# pnode.net
KiCad netlist of a schematic drawn in EAGLE
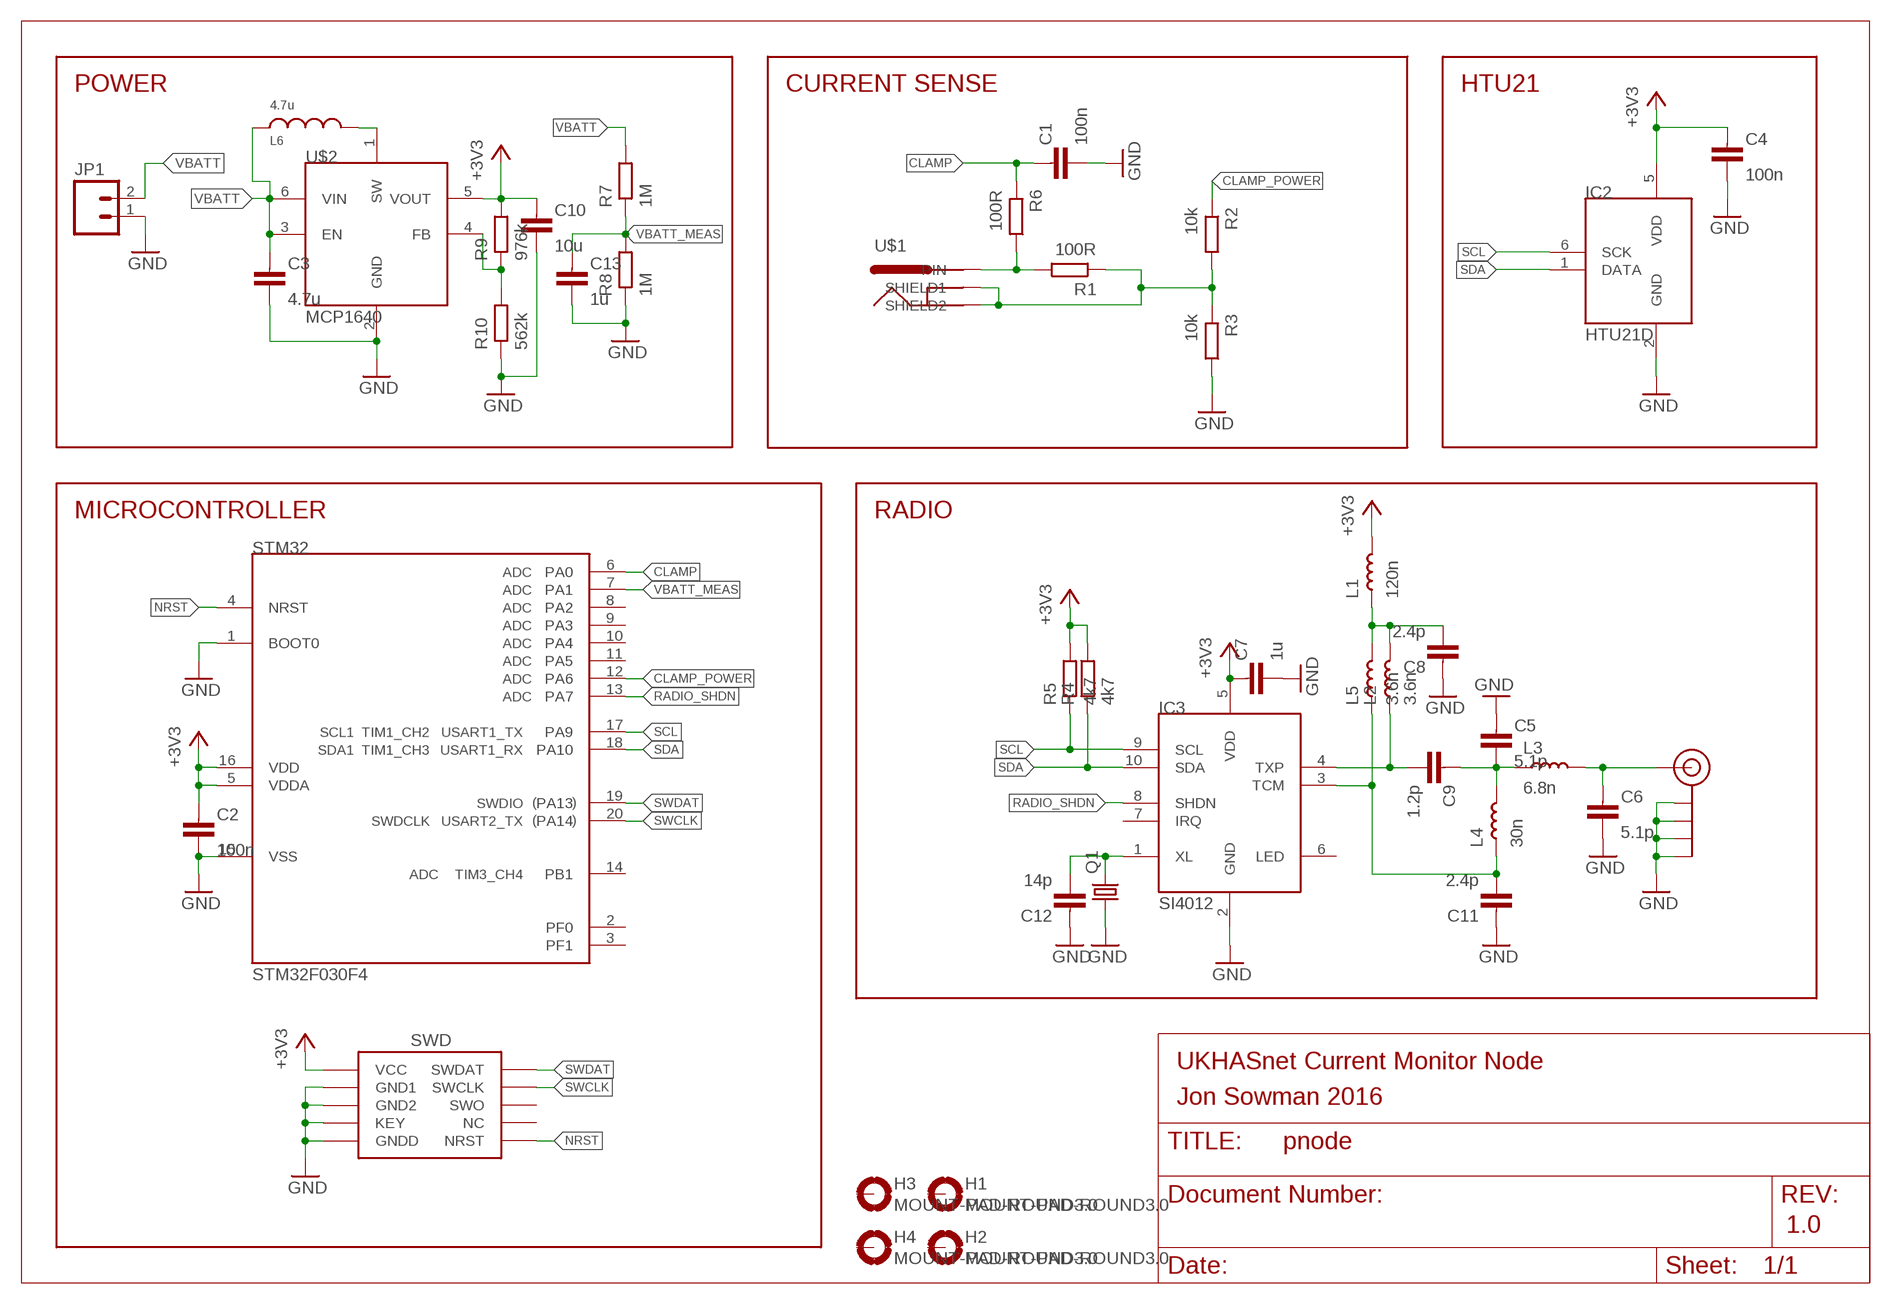
[diagram p0: schematic, sheet 1]

(export (version "E")
  (design (tool "Eeschema 10.0.6"))
  (components
    (comp (ref "C1")
      (value "100n")
      (footprint "eagle-import:C0603-N")
      (libsource (lib "eagle-import") (part "CAPACITOR0603-N"))
    )
    (comp (ref "C2")
      (value "100n")
      (footprint "eagle-import:C0603-N")
      (libsource (lib "eagle-import") (part "CAPACITOR0603-N"))
    )
    (comp (ref "C3")
      (value "4.7u")
      (footprint "eagle-import:C0603-N")
      (libsource (lib "eagle-import") (part "CAPACITOR0603-N"))
    )
    (comp (ref "C4")
      (value "100n")
      (footprint "eagle-import:C0603-N")
      (libsource (lib "eagle-import") (part "CAPACITOR0603-N"))
    )
    (comp (ref "C5")
      (value "5.1p")
      (footprint "eagle-import:C0603-N")
      (libsource (lib "eagle-import") (part "CAPACITOR0603-N"))
    )
    (comp (ref "C6")
      (value "5.1p")
      (footprint "eagle-import:C0603-N")
      (libsource (lib "eagle-import") (part "CAPACITOR0603-N"))
    )
    (comp (ref "C7")
      (value "1u")
      (footprint "eagle-import:C0603-N")
      (libsource (lib "eagle-import") (part "CAPACITOR0603-N"))
    )
    (comp (ref "C8")
      (value "2.4p")
      (footprint "eagle-import:C0603-N")
      (libsource (lib "eagle-import") (part "CAPACITOR0603-N"))
    )
    (comp (ref "C9")
      (value "1.2p")
      (footprint "eagle-import:C0603-N")
      (libsource (lib "eagle-import") (part "CAPACITOR0603-N"))
    )
    (comp (ref "C10")
      (value "10u")
      (footprint "eagle-import:C0603-N")
      (libsource (lib "eagle-import") (part "CAPACITOR0603-N"))
    )
    (comp (ref "C11")
      (value "2.4p")
      (footprint "eagle-import:C0603-N")
      (libsource (lib "eagle-import") (part "CAPACITOR0603-N"))
    )
    (comp (ref "C12")
      (value "14p")
      (footprint "eagle-import:C0603-N")
      (libsource (lib "eagle-import") (part "CAPACITOR0603-N"))
    )
    (comp (ref "C13")
      (value "1u")
      (footprint "eagle-import:C0603-N")
      (libsource (lib "eagle-import") (part "CAPACITOR0603-N"))
    )
    (comp (ref "H1")
      (value "MOUNT-PAD-ROUND3.0")
      (footprint "eagle-import:3,0-PAD")
      (libsource (lib "eagle-import") (part "MOUNT-PAD-ROUND3.0"))
    )
    (comp (ref "H2")
      (value "MOUNT-PAD-ROUND3.0")
      (footprint "eagle-import:3,0-PAD")
      (libsource (lib "eagle-import") (part "MOUNT-PAD-ROUND3.0"))
    )
    (comp (ref "H3")
      (value "MOUNT-PAD-ROUND3.0")
      (footprint "eagle-import:3,0-PAD")
      (libsource (lib "eagle-import") (part "MOUNT-PAD-ROUND3.0"))
    )
    (comp (ref "H4")
      (value "MOUNT-PAD-ROUND3.0")
      (footprint "eagle-import:3,0-PAD")
      (libsource (lib "eagle-import") (part "MOUNT-PAD-ROUND3.0"))
    )
    (comp (ref "IC2")
      (value "HTU21D")
      (footprint "eagle-import:DFN6-L")
      (libsource (lib "eagle-import") (part "HTU21D"))
    )
    (comp (ref "IC3")
      (value "SI4012")
      (footprint "eagle-import:MSOP10")
      (libsource (lib "eagle-import") (part "SI4012"))
    )
    (comp (ref "J$1")
      (value "SMA_EDGE")
      (footprint "eagle-import:SMA-EDGE")
      (libsource (lib "eagle-import") (part "SMA_EDGE"))
    )
    (comp (ref "JP1")
      (value "M02PTH")
      (footprint "eagle-import:1X02")
      (libsource (lib "eagle-import") (part "M02PTH"))
    )
    (comp (ref "L1")
      (value "120n")
      (footprint "eagle-import:L0603-N")
      (libsource (lib "eagle-import") (part "INDUCTOR0603-N"))
    )
    (comp (ref "L2")
      (value "3.6n")
      (footprint "eagle-import:L0402-N")
      (libsource (lib "eagle-import") (part "INDUCTOR0402-N"))
    )
    (comp (ref "L3")
      (value "6.8n")
      (footprint "eagle-import:L0402-N")
      (libsource (lib "eagle-import") (part "INDUCTOR0402-N"))
    )
    (comp (ref "L4")
      (value "30n")
      (footprint "eagle-import:L0402-N")
      (libsource (lib "eagle-import") (part "INDUCTOR0402-N"))
    )
    (comp (ref "L5")
      (value "3.6n")
      (footprint "eagle-import:L0402-N")
      (libsource (lib "eagle-import") (part "INDUCTOR0402-N"))
    )
    (comp (ref "L6")
      (value "4.7u")
      (footprint "eagle-import:BOURNS_SDE0403A")
      (libsource (lib "eagle-import") (part "BOURNS_SDE0403A"))
    )
    (comp (ref "Q1")
      (value "CRYSTALHC49S")
      (footprint "eagle-import:HC49_S")
      (libsource (lib "eagle-import") (part "CRYSTALHC49S"))
    )
    (comp (ref "R1")
      (value "100R")
      (footprint "eagle-import:R0603-N")
      (libsource (lib "eagle-import") (part "RESISTOR0603-N"))
    )
    (comp (ref "R2")
      (value "10k")
      (footprint "eagle-import:R0603-N")
      (libsource (lib "eagle-import") (part "RESISTOR0603-N"))
    )
    (comp (ref "R3")
      (value "10k")
      (footprint "eagle-import:R0603-N")
      (libsource (lib "eagle-import") (part "RESISTOR0603-N"))
    )
    (comp (ref "R4")
      (value "4k7")
      (footprint "eagle-import:R0603-N")
      (libsource (lib "eagle-import") (part "RESISTOR0603-N"))
    )
    (comp (ref "R5")
      (value "4k7")
      (footprint "eagle-import:R0603-N")
      (libsource (lib "eagle-import") (part "RESISTOR0603-N"))
    )
    (comp (ref "R6")
      (value "100R")
      (footprint "eagle-import:R0603-N")
      (libsource (lib "eagle-import") (part "RESISTOR0603-N"))
    )
    (comp (ref "R7")
      (value "1M")
      (footprint "eagle-import:R0603-N")
      (libsource (lib "eagle-import") (part "RESISTOR0603-N"))
    )
    (comp (ref "R8")
      (value "1M")
      (footprint "eagle-import:R0603-N")
      (libsource (lib "eagle-import") (part "RESISTOR0603-N"))
    )
    (comp (ref "R9")
      (value "976k")
      (footprint "eagle-import:R0603-N")
      (libsource (lib "eagle-import") (part "RESISTOR0603-N"))
    )
    (comp (ref "R10")
      (value "562k")
      (footprint "eagle-import:R0603-N")
      (libsource (lib "eagle-import") (part "RESISTOR0603-N"))
    )
    (comp (ref "STM32")
      (value "STM32F030F4")
      (footprint "eagle-import:TSSOP20")
      (libsource (lib "eagle-import") (part "STM32F030F4"))
    )
    (comp (ref "U$1")
      (value "13MM_DC_JACKPTH")
      (footprint "eagle-import:13MM_DC_JACK")
      (libsource (lib "eagle-import") (part "13MM_DC_JACKPTH"))
    )
    (comp (ref "U$2")
      (value "MCP1640")
      (footprint "eagle-import:SOT23-6")
      (libsource (lib "eagle-import") (part "MCP1640"))
    )
    (comp (ref "U$3")
      (value "SWD_PTH_SHROUD")
      (footprint "eagle-import:SWD_PTH_SHROUD")
      (libsource (lib "eagle-import") (part "SWD_PTH_SHROUD"))
    )
  )
  (nets
    (net (code "1") (name "+3V3") (class "Default")
      (node (ref "C10") (pin "1") (pinfunction "1_1") (pintype "passive"))
      (node (ref "C2") (pin "1") (pinfunction "1_1") (pintype "passive"))
      (node (ref "C4") (pin "1") (pinfunction "1_1") (pintype "passive"))
      (node (ref "C7") (pin "1") (pinfunction "1_1") (pintype "passive"))
      (node (ref "IC2") (pin "5") (pinfunction "VDD_5") (pintype "power_in"))
      (node (ref "IC3") (pin "5") (pinfunction "VDD_5") (pintype "power_in"))
      (node (ref "L1") (pin "2") (pinfunction "P$2_2") (pintype "passive"))
      (node (ref "R4") (pin "2") (pinfunction "P$2_2") (pintype "passive"))
      (node (ref "R5") (pin "2") (pinfunction "P$2_2") (pintype "passive"))
      (node (ref "R9") (pin "2") (pinfunction "P$2_2") (pintype "passive"))
      (node (ref "STM32") (pin "16") (pinfunction "VDD_16") (pintype "power_in"))
      (node (ref "STM32") (pin "5") (pinfunction "VDDA_5") (pintype "power_in"))
      (node (ref "U$2") (pin "5") (pinfunction "VOUT_5") (pintype "output"))
      (node (ref "U$3") (pin "1") (pinfunction "VCC_1") (pintype "power_in"))
    )
    (net (code "2") (name "CLAMP") (class "Default")
      (node (ref "C1") (pin "1") (pinfunction "1_1") (pintype "passive"))
      (node (ref "R6") (pin "1") (pinfunction "P$1_1") (pintype "passive"))
      (node (ref "STM32") (pin "6") (pinfunction "PA0_6") (pintype "bidirectional"))
    )
    (net (code "3") (name "CLAMP_POWER") (class "Default")
      (node (ref "R2") (pin "1") (pinfunction "P$1_1") (pintype "passive"))
      (node (ref "STM32") (pin "12") (pinfunction "PA6_12") (pintype "bidirectional"))
    )
    (net (code "4") (name "GND") (class "Default")
      (node (ref "C1") (pin "2") (pinfunction "2_2") (pintype "passive"))
      (node (ref "C10") (pin "2") (pinfunction "2_2") (pintype "passive"))
      (node (ref "C11") (pin "1") (pinfunction "1_1") (pintype "passive"))
      (node (ref "C12") (pin "1") (pinfunction "1_1") (pintype "passive"))
      (node (ref "C13") (pin "2") (pinfunction "2_2") (pintype "passive"))
      (node (ref "C2") (pin "2") (pinfunction "2_2") (pintype "passive"))
      (node (ref "C3") (pin "2") (pinfunction "2_2") (pintype "passive"))
      (node (ref "C4") (pin "2") (pinfunction "2_2") (pintype "passive"))
      (node (ref "C5") (pin "1") (pinfunction "1_1") (pintype "passive"))
      (node (ref "C6") (pin "2") (pinfunction "2_2") (pintype "passive"))
      (node (ref "C7") (pin "2") (pinfunction "2_2") (pintype "passive"))
      (node (ref "C8") (pin "1") (pinfunction "1_1") (pintype "passive"))
      (node (ref "IC2") (pin "2") (pinfunction "GND_2") (pintype "power_in"))
      (node (ref "IC3") (pin "2") (pinfunction "GND_2") (pintype "power_in"))
      (node (ref "J$1") (pin "GND@0") (pinfunction "GND_GND@0") (pintype "bidirectional"))
      (node (ref "J$1") (pin "GND@1") (pinfunction "GND_GND@1") (pintype "bidirectional"))
      (node (ref "J$1") (pin "GND@2") (pinfunction "GND_GND@2") (pintype "bidirectional"))
      (node (ref "J$1") (pin "GND@3") (pinfunction "GND_GND@3") (pintype "bidirectional"))
      (node (ref "JP1") (pin "1") (pinfunction "1_1") (pintype "passive"))
      (node (ref "Q1") (pin "1") (pinfunction "1_1") (pintype "passive"))
      (node (ref "R10") (pin "1") (pinfunction "P$1_1") (pintype "passive"))
      (node (ref "R3") (pin "2") (pinfunction "P$2_2") (pintype "passive"))
      (node (ref "R8") (pin "1") (pinfunction "P$1_1") (pintype "passive"))
      (node (ref "STM32") (pin "1") (pinfunction "BOOT0_1") (pintype "input"))
      (node (ref "STM32") (pin "15") (pinfunction "VSS_15") (pintype "power_in"))
      (node (ref "U$2") (pin "2") (pinfunction "GND_2") (pintype "power_in"))
      (node (ref "U$3") (pin "3") (pinfunction "GND1_3") (pintype "power_in"))
      (node (ref "U$3") (pin "5") (pinfunction "GND2_5") (pintype "power_in"))
      (node (ref "U$3") (pin "7") (pinfunction "KEY_7") (pintype "bidirectional"))
      (node (ref "U$3") (pin "9") (pinfunction "GNDD_9") (pintype "power_in"))
    )
    (net (code "5") (name "NRST") (class "Default")
      (node (ref "STM32") (pin "4") (pinfunction "NRST_4") (pintype "input"))
      (node (ref "U$3") (pin "10") (pinfunction "NRST_10") (pintype "bidirectional"))
    )
    (net (code "6") (name "Net-(IC3-TCM)") (class "Default")
      (node (ref "C11") (pin "2") (pinfunction "2_2") (pintype "passive"))
      (node (ref "IC3") (pin "3") (pinfunction "TCM_3") (pintype "output"))
      (node (ref "L4") (pin "1") (pinfunction "P$1_1") (pintype "passive"))
      (node (ref "L5") (pin "1") (pinfunction "P$1_1") (pintype "passive"))
    )
    (net (code "7") (name "Net-(IC3-TXP)") (class "Default")
      (node (ref "C9") (pin "2") (pinfunction "2_2") (pintype "passive"))
      (node (ref "IC3") (pin "4") (pinfunction "TXP_4") (pintype "output"))
      (node (ref "L2") (pin "1") (pinfunction "P$1_1") (pintype "passive"))
    )
    (net (code "8") (name "Net-(IC3-XL)") (class "Default")
      (node (ref "C12") (pin "2") (pinfunction "2_2") (pintype "passive"))
      (node (ref "IC3") (pin "1") (pinfunction "XL_1") (pintype "bidirectional"))
      (node (ref "Q1") (pin "2") (pinfunction "2_2") (pintype "passive"))
    )
    (net (code "9") (name "Net-(J$1-SIGNAL)") (class "Default")
      (node (ref "C6") (pin "1") (pinfunction "1_1") (pintype "passive"))
      (node (ref "J$1") (pin "SIG") (pinfunction "SIGNAL_SIG") (pintype "bidirectional"))
      (node (ref "L3") (pin "2") (pinfunction "P$2_2") (pintype "passive"))
    )
    (net (code "10") (name "Net-(L1-P$1)") (class "Default")
      (node (ref "C8") (pin "2") (pinfunction "2_2") (pintype "passive"))
      (node (ref "L1") (pin "1") (pinfunction "P$1_1") (pintype "passive"))
      (node (ref "L2") (pin "2") (pinfunction "P$2_2") (pintype "passive"))
      (node (ref "L5") (pin "2") (pinfunction "P$2_2") (pintype "passive"))
    )
    (net (code "11") (name "Net-(L3-P$1)") (class "Default")
      (node (ref "C5") (pin "2") (pinfunction "2_2") (pintype "passive"))
      (node (ref "C9") (pin "1") (pinfunction "1_1") (pintype "passive"))
      (node (ref "L3") (pin "1") (pinfunction "P$1_1") (pintype "passive"))
      (node (ref "L4") (pin "2") (pinfunction "P$2_2") (pintype "passive"))
    )
    (net (code "12") (name "Net-(R1-P$1)") (class "Default")
      (node (ref "R1") (pin "1") (pinfunction "P$1_1") (pintype "passive"))
      (node (ref "R2") (pin "2") (pinfunction "P$2_2") (pintype "passive"))
      (node (ref "R3") (pin "1") (pinfunction "P$1_1") (pintype "passive"))
      (node (ref "U$1") (pin "2") (pinfunction "SHIELD1_2") (pintype "bidirectional"))
      (node (ref "U$1") (pin "3") (pinfunction "SHIELD2_3") (pintype "bidirectional"))
    )
    (net (code "13") (name "Net-(R1-P$2)") (class "Default")
      (node (ref "R1") (pin "2") (pinfunction "P$2_2") (pintype "passive"))
      (node (ref "R6") (pin "2") (pinfunction "P$2_2") (pintype "passive"))
      (node (ref "U$1") (pin "1") (pinfunction "PIN_1") (pintype "bidirectional"))
    )
    (net (code "14") (name "Net-(R10-P$2)") (class "Default")
      (node (ref "R10") (pin "2") (pinfunction "P$2_2") (pintype "passive"))
      (node (ref "R9") (pin "1") (pinfunction "P$1_1") (pintype "passive"))
      (node (ref "U$2") (pin "4") (pinfunction "FB_4") (pintype "input"))
    )
    (net (code "15") (name "Net-(U$2-SW)") (class "Default")
      (node (ref "L6") (pin "P$2") (pinfunction "P$2_P$2") (pintype "bidirectional"))
      (node (ref "U$2") (pin "1") (pinfunction "SW_1") (pintype "input"))
    )
    (net (code "16") (name "RADIO_SHDN") (class "Default")
      (node (ref "IC3") (pin "8") (pinfunction "SHDN_8") (pintype "input"))
      (node (ref "STM32") (pin "13") (pinfunction "PA7_13") (pintype "bidirectional"))
    )
    (net (code "17") (name "SCL") (class "Default")
      (node (ref "IC2") (pin "6") (pinfunction "SCK_6") (pintype "input"))
      (node (ref "IC3") (pin "9") (pinfunction "SCL_9") (pintype "input"))
      (node (ref "R5") (pin "1") (pinfunction "P$1_1") (pintype "passive"))
      (node (ref "STM32") (pin "17") (pinfunction "PA9_17") (pintype "bidirectional"))
    )
    (net (code "18") (name "SDA") (class "Default")
      (node (ref "IC2") (pin "1") (pinfunction "DATA_1") (pintype "bidirectional"))
      (node (ref "IC3") (pin "10") (pinfunction "SDA_10") (pintype "bidirectional"))
      (node (ref "R4") (pin "1") (pinfunction "P$1_1") (pintype "passive"))
      (node (ref "STM32") (pin "18") (pinfunction "PA10_18") (pintype "bidirectional"))
    )
    (net (code "19") (name "SWCLK") (class "Default")
      (node (ref "STM32") (pin "20") (pinfunction "PA14_20") (pintype "bidirectional"))
      (node (ref "U$3") (pin "4") (pinfunction "SWCLK_4") (pintype "bidirectional"))
    )
    (net (code "20") (name "SWDAT") (class "Default")
      (node (ref "STM32") (pin "19") (pinfunction "PA13_19") (pintype "bidirectional"))
      (node (ref "U$3") (pin "2") (pinfunction "SWDAT_2") (pintype "bidirectional"))
    )
    (net (code "21") (name "VBATT") (class "Default")
      (node (ref "C3") (pin "1") (pinfunction "1_1") (pintype "passive"))
      (node (ref "JP1") (pin "2") (pinfunction "2_2") (pintype "passive"))
      (node (ref "L6") (pin "P$1") (pinfunction "P$1_P$1") (pintype "bidirectional"))
      (node (ref "R7") (pin "2") (pinfunction "P$2_2") (pintype "passive"))
      (node (ref "U$2") (pin "3") (pinfunction "EN_3") (pintype "input"))
      (node (ref "U$2") (pin "6") (pinfunction "VIN_6") (pintype "power_in"))
    )
    (net (code "22") (name "VBATT_MEAS") (class "Default")
      (node (ref "C13") (pin "1") (pinfunction "1_1") (pintype "passive"))
      (node (ref "R7") (pin "1") (pinfunction "P$1_1") (pintype "passive"))
      (node (ref "R8") (pin "2") (pinfunction "P$2_2") (pintype "passive"))
      (node (ref "STM32") (pin "7") (pinfunction "PA1_7") (pintype "bidirectional"))
    )
    (net (code "23") (name "unconnected-(H1-MOUNT-PadB3,0)") (class "Default")
      (node (ref "H1") (pin "B3,0") (pinfunction "MOUNT_B3,0") (pintype "passive"))
    )
    (net (code "24") (name "unconnected-(H2-MOUNT-PadB3,0)") (class "Default")
      (node (ref "H2") (pin "B3,0") (pinfunction "MOUNT_B3,0") (pintype "passive"))
    )
    (net (code "25") (name "unconnected-(H3-MOUNT-PadB3,0)") (class "Default")
      (node (ref "H3") (pin "B3,0") (pinfunction "MOUNT_B3,0") (pintype "passive"))
    )
    (net (code "26") (name "unconnected-(H4-MOUNT-PadB3,0)") (class "Default")
      (node (ref "H4") (pin "B3,0") (pinfunction "MOUNT_B3,0") (pintype "passive"))
    )
    (net (code "27") (name "unconnected-(IC3-IRQ-Pad7)") (class "Default")
      (node (ref "IC3") (pin "7") (pinfunction "IRQ_7") (pintype "output"))
    )
    (net (code "28") (name "unconnected-(IC3-LED-Pad6)") (class "Default")
      (node (ref "IC3") (pin "6") (pinfunction "LED_6") (pintype "output"))
    )
    (net (code "29") (name "unconnected-(STM32-PA2-Pad8)") (class "Default")
      (node (ref "STM32") (pin "8") (pinfunction "PA2_8") (pintype "bidirectional"))
    )
    (net (code "30") (name "unconnected-(STM32-PA3-Pad9)") (class "Default")
      (node (ref "STM32") (pin "9") (pinfunction "PA3_9") (pintype "bidirectional"))
    )
    (net (code "31") (name "unconnected-(STM32-PA4-Pad10)") (class "Default")
      (node (ref "STM32") (pin "10") (pinfunction "PA4_10") (pintype "bidirectional"))
    )
    (net (code "32") (name "unconnected-(STM32-PA5-Pad11)") (class "Default")
      (node (ref "STM32") (pin "11") (pinfunction "PA5_11") (pintype "bidirectional"))
    )
    (net (code "33") (name "unconnected-(STM32-PB1-Pad14)") (class "Default")
      (node (ref "STM32") (pin "14") (pinfunction "PB1_14") (pintype "bidirectional"))
    )
    (net (code "34") (name "unconnected-(STM32-PF0-Pad2)") (class "Default")
      (node (ref "STM32") (pin "2") (pinfunction "PF0_2") (pintype "bidirectional"))
    )
    (net (code "35") (name "unconnected-(STM32-PF1-Pad3)") (class "Default")
      (node (ref "STM32") (pin "3") (pinfunction "PF1_3") (pintype "bidirectional"))
    )
    (net (code "36") (name "unconnected-(U$3-NC-Pad8)") (class "Default")
      (node (ref "U$3") (pin "8") (pinfunction "NC_8") (pintype "no_connect"))
    )
    (net (code "37") (name "unconnected-(U$3-SWO-Pad6)") (class "Default")
      (node (ref "U$3") (pin "6") (pinfunction "SWO_6") (pintype "bidirectional"))
    )
  )
)
